# UnoShieldBasic.net
KiCad netlist of a schematic drawn in EAGLE
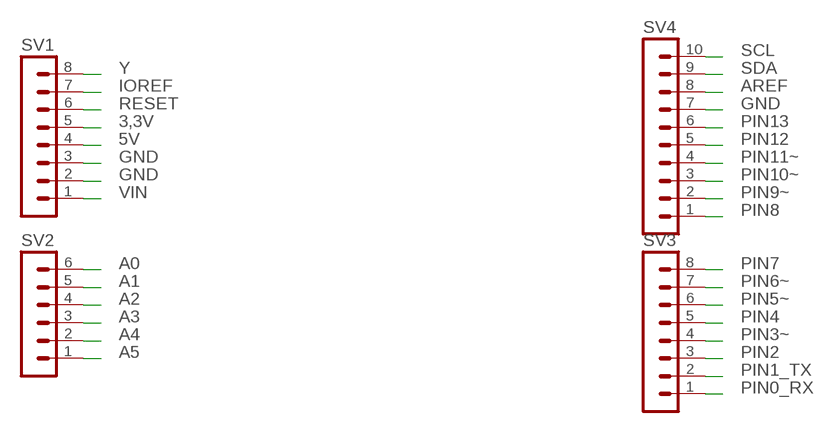
[diagram p0: schematic, sheet 1]

(export (version "E")
  (design (tool "Eeschema 10.0.6"))
  (components
    (comp (ref "SV1")
      (value "MA08-1")
      (footprint "eagle-import:MA08-1")
      (libsource (lib "eagle-import") (part "MA08-1"))
    )
    (comp (ref "SV2")
      (value "MA06-1")
      (footprint "eagle-import:MA06-1")
      (libsource (lib "eagle-import") (part "MA06-1"))
    )
    (comp (ref "SV3")
      (value "MA08-1")
      (footprint "eagle-import:MA08-1")
      (libsource (lib "eagle-import") (part "MA08-1"))
    )
    (comp (ref "SV4")
      (value "MA10-1")
      (footprint "eagle-import:MA10-1")
      (libsource (lib "eagle-import") (part "MA10-1"))
    )
  )
  (nets
    (net (code "1") (name "/3,3V") (class "Default")
      (node (ref "SV1") (pin "5") (pinfunction "5_5") (pintype "passive"))
    )
    (net (code "2") (name "/5V") (class "Default")
      (node (ref "SV1") (pin "4") (pinfunction "4_4") (pintype "passive"))
    )
    (net (code "3") (name "/A0") (class "Default")
      (node (ref "SV2") (pin "6") (pinfunction "6_6") (pintype "passive"))
    )
    (net (code "4") (name "/A1") (class "Default")
      (node (ref "SV2") (pin "5") (pinfunction "5_5") (pintype "passive"))
    )
    (net (code "5") (name "/A2") (class "Default")
      (node (ref "SV2") (pin "4") (pinfunction "4_4") (pintype "passive"))
    )
    (net (code "6") (name "/A3") (class "Default")
      (node (ref "SV2") (pin "3") (pinfunction "3_3") (pintype "passive"))
    )
    (net (code "7") (name "/A4") (class "Default")
      (node (ref "SV2") (pin "2") (pinfunction "2_2") (pintype "passive"))
    )
    (net (code "8") (name "/A5") (class "Default")
      (node (ref "SV2") (pin "1") (pinfunction "1_1") (pintype "passive"))
    )
    (net (code "9") (name "/AREF") (class "Default")
      (node (ref "SV4") (pin "8") (pinfunction "8_8") (pintype "passive"))
    )
    (net (code "10") (name "/GND") (class "Default")
      (node (ref "SV1") (pin "2") (pinfunction "2_2") (pintype "passive"))
      (node (ref "SV1") (pin "3") (pinfunction "3_3") (pintype "passive"))
      (node (ref "SV4") (pin "7") (pinfunction "7_7") (pintype "passive"))
    )
    (net (code "11") (name "/IOREF") (class "Default")
      (node (ref "SV1") (pin "7") (pinfunction "7_7") (pintype "passive"))
    )
    (net (code "12") (name "/PIN0_RX") (class "Default")
      (node (ref "SV3") (pin "1") (pinfunction "1_1") (pintype "passive"))
    )
    (net (code "13") (name "/PIN1_TX") (class "Default")
      (node (ref "SV3") (pin "2") (pinfunction "2_2") (pintype "passive"))
    )
    (net (code "14") (name "/PIN2") (class "Default")
      (node (ref "SV3") (pin "3") (pinfunction "3_3") (pintype "passive"))
    )
    (net (code "15") (name "/PIN3~{}") (class "Default")
      (node (ref "SV3") (pin "4") (pinfunction "4_4") (pintype "passive"))
    )
    (net (code "16") (name "/PIN4") (class "Default")
      (node (ref "SV3") (pin "5") (pinfunction "5_5") (pintype "passive"))
    )
    (net (code "17") (name "/PIN5~{}") (class "Default")
      (node (ref "SV3") (pin "6") (pinfunction "6_6") (pintype "passive"))
    )
    (net (code "18") (name "/PIN6~{}") (class "Default")
      (node (ref "SV3") (pin "7") (pinfunction "7_7") (pintype "passive"))
    )
    (net (code "19") (name "/PIN7") (class "Default")
      (node (ref "SV3") (pin "8") (pinfunction "8_8") (pintype "passive"))
    )
    (net (code "20") (name "/PIN8") (class "Default")
      (node (ref "SV4") (pin "1") (pinfunction "1_1") (pintype "passive"))
    )
    (net (code "21") (name "/PIN9~{}") (class "Default")
      (node (ref "SV4") (pin "2") (pinfunction "2_2") (pintype "passive"))
    )
    (net (code "22") (name "/PIN10~{}") (class "Default")
      (node (ref "SV4") (pin "3") (pinfunction "3_3") (pintype "passive"))
    )
    (net (code "23") (name "/PIN11~{}") (class "Default")
      (node (ref "SV4") (pin "4") (pinfunction "4_4") (pintype "passive"))
    )
    (net (code "24") (name "/PIN12") (class "Default")
      (node (ref "SV4") (pin "5") (pinfunction "5_5") (pintype "passive"))
    )
    (net (code "25") (name "/PIN13") (class "Default")
      (node (ref "SV4") (pin "6") (pinfunction "6_6") (pintype "passive"))
    )
    (net (code "26") (name "/RESET") (class "Default")
      (node (ref "SV1") (pin "6") (pinfunction "6_6") (pintype "passive"))
    )
    (net (code "27") (name "/SCL") (class "Default")
      (node (ref "SV4") (pin "10") (pinfunction "10_10") (pintype "passive"))
    )
    (net (code "28") (name "/SDA") (class "Default")
      (node (ref "SV4") (pin "9") (pinfunction "9_9") (pintype "passive"))
    )
    (net (code "29") (name "/VIN") (class "Default")
      (node (ref "SV1") (pin "1") (pinfunction "1_1") (pintype "passive"))
    )
    (net (code "30") (name "/Y") (class "Default")
      (node (ref "SV1") (pin "8") (pinfunction "8_8") (pintype "passive"))
    )
  )
)
